# Cell.net
KiCad netlist of a schematic drawn in Altium Designer
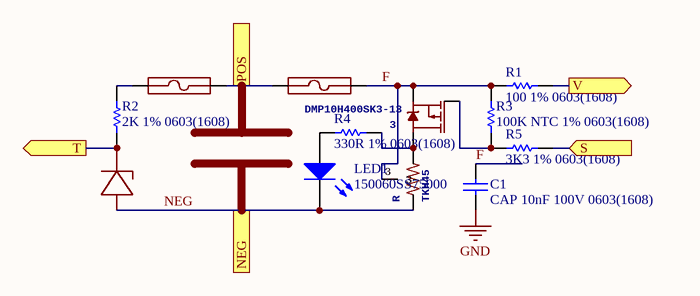
[diagram p0: Cell.SchDoc]

(export (version "E")
  (design (tool "Eeschema 10.0.6"))
  (components
    (comp (ref "3")
      (value "DMP10H400SK3-13")
      (footprint "TO252")
      (fields (field (name "LIBRARYNAME") "IFE_Transistors"))
      (libsource (lib "IFE_Transistors") (part "DMP10H400SK3-13"))
    )
    (comp (ref "C1")
      (value "CAP 10nF 100V 0603(1608)")
      (footprint "CAPC0603(1608)100_N")
      (description "CAP 10nF 100V ±5% 0603 (1608 Metric) Thickness 1mm SMD")
      (fields (field (name "TOLERANCE") "Â±5%"))
      (libsource (lib "Altium Content Vault") (part "CAP"))
    )
    (comp (ref "CELL+")
      (value "LI6PT")
      (footprint "6PT")
      (fields (field (name "LIBRARYNAME") "IFE_Energus"))
      (libsource (lib "IFE_Energus") (part "LI6PT"))
    )
    (comp (ref "F1")
      (value "0679L")
      (footprint "2410SMD")
      (fields (field (name "LIBRARYNAME") "IFE_Fuses"))
      (libsource (lib "IFE_Fuses") (part "0679L"))
    )
    (comp (ref "F2")
      (value "0679L")
      (footprint "2410SMD")
      (fields (field (name "LIBRARYNAME") "IFE_Fuses"))
      (libsource (lib "IFE_Fuses") (part "0679L"))
    )
    (comp (ref "LED1")
      (value "150060SS75000")
      (footprint "0603_A")
      (description "SMD mono-color Chip LED, WL-SMCW, Super Red")
      (fields (field (name "MANUFACTURER") "Wuerth Elektronik"))
      (libsource (lib "Altium Content Vault") (part "WE-LED_K1A2-2"))
    )
    (comp (ref "R")
      (value "TKH45")
      (footprint "TO252-TKH-45")
      (fields (field (name "LIBRARYNAME") "IFE_Resistors"))
      (libsource (lib "IFE_Resistors") (part "TKH45"))
    )
    (comp (ref "R1")
      (value "100 1% 0603(1608)")
      (footprint "RESC0603(1608)_L")
      (description "100R 0.1W 1% 0603 (1608 Metric)  SMD")
      (fields (field (name "POWER") "0.1 W") (field (name "TOLERANCE") "1 %"))
      (libsource (lib "Altium Content Vault") (part "RES"))
    )
    (comp (ref "R2")
      (value "2K 1% 0603(1608)")
      (footprint "RESC0603(1608)_L")
      (description "2R94 0.1W 1% 0603 (1608 Metric)  SMD")
      (fields (field (name "POWER") "0.1 W") (field (name "TOLERANCE") "1 %"))
      (libsource (lib "Altium Content Vault") (part "RES"))
    )
    (comp (ref "R3")
      (value "100K NTC 1% 0603(1608)")
      (footprint "RESC0603(1608)_L")
      (description "2R94 0.1W 1% 0603 (1608 Metric)  SMD")
      (fields (field (name "POWER") "0.1 W") (field (name "TOLERANCE") "1 %"))
      (libsource (lib "Altium Content Vault") (part "RES"))
    )
    (comp (ref "R4")
      (value "330R 1% 0603(1608)")
      (footprint "RESC0603(1608)_L")
      (description "2R94 0.1W 1% 0603 (1608 Metric)  SMD")
      (fields (field (name "POWER") "0.1 W") (field (name "TOLERANCE") "1 %"))
      (libsource (lib "Altium Content Vault") (part "RES"))
    )
    (comp (ref "R5")
      (value "3K3 1% 0603(1608)")
      (footprint "RESC0603(1608)_L")
      (description "2R94 0.1W 1% 0603 (1608 Metric)  SMD")
      (fields (field (name "POWER") "0.1 W") (field (name "TOLERANCE") "1 %"))
      (libsource (lib "Altium Content Vault") (part "RES"))
    )
  )
  (nets
    (net (code "1") (name "/F") (class "Default")
      (node (ref "3") (pin "3") (pinfunction "S_3") (pintype "passive"))
      (node (ref "C1") (pin "2") (pinfunction "2_2") (pintype "passive"))
      (node (ref "F2") (pin "P$2") (pinfunction "P$2_P$2") (pintype "passive"))
      (node (ref "R") (pin "3") (pinfunction "3_3") (pintype "passive"))
      (node (ref "R1") (pin "2") (pinfunction "2_2") (pintype "passive"))
      (node (ref "R3") (pin "2") (pinfunction "2_2") (pintype "passive"))
    )
    (net (code "2") (name "/NEG") (class "Default")
      (node (ref "CELL+") (pin "2") (pinfunction "TEMP-_2") (pintype "passive"))
      (node (ref "CELL+") (pin "CELL-") (pinfunction "CELL-_CELL-") (pintype "passive"))
      (node (ref "LED1") (pin "1") (pinfunction "K_1") (pintype "passive"))
      (node (ref "R") (pin "1") (pinfunction "1_1") (pintype "passive"))
    )
    (net (code "3") (name "/POS") (class "Default")
      (node (ref "CELL+") (pin "CELL+") (pinfunction "CELL+_CELL+") (pintype "passive"))
      (node (ref "F1") (pin "P$2") (pinfunction "P$2_P$2") (pintype "passive"))
      (node (ref "F2") (pin "P$1") (pinfunction "P$1_P$1") (pintype "passive"))
    )
    (net (code "4") (name "/S") (class "Default")
      (node (ref "R5") (pin "1") (pinfunction "1_1") (pintype "passive"))
    )
    (net (code "5") (name "/T") (class "Default")
      (node (ref "CELL+") (pin "1") (pinfunction "TEMP+_1") (pintype "passive"))
      (node (ref "R2") (pin "1") (pinfunction "1_1") (pintype "passive"))
    )
    (net (code "6") (name "/V") (class "Default")
      (node (ref "R1") (pin "1") (pinfunction "1_1") (pintype "passive"))
    )
    (net (code "7") (name "GND") (class "Default")
      (node (ref "C1") (pin "1") (pinfunction "1_1") (pintype "passive"))
    )
    (net (code "8") (name "Net-(3-D)") (class "Default")
      (node (ref "3") (pin "2") (pinfunction "D_2") (pintype "passive"))
      (node (ref "R") (pin "2") (pinfunction "2_2") (pintype "passive"))
      (node (ref "R4") (pin "1") (pinfunction "1_1") (pintype "passive"))
    )
    (net (code "9") (name "Net-(3-G)") (class "Default")
      (node (ref "3") (pin "1") (pinfunction "G_1") (pintype "passive"))
      (node (ref "R3") (pin "1") (pinfunction "1_1") (pintype "passive"))
      (node (ref "R5") (pin "2") (pinfunction "2_2") (pintype "passive"))
    )
    (net (code "10") (name "Net-(F1-PadP$1)") (class "Default")
      (node (ref "F1") (pin "P$1") (pinfunction "P$1_P$1") (pintype "passive"))
      (node (ref "R2") (pin "2") (pinfunction "2_2") (pintype "passive"))
    )
    (net (code "11") (name "Net-(LED1-A)") (class "Default")
      (node (ref "LED1") (pin "2") (pinfunction "A_2") (pintype "passive"))
      (node (ref "R4") (pin "2") (pinfunction "2_2") (pintype "passive"))
    )
  )
)
